# schematicEagle.net
KiCad netlist of a schematic drawn in EAGLE
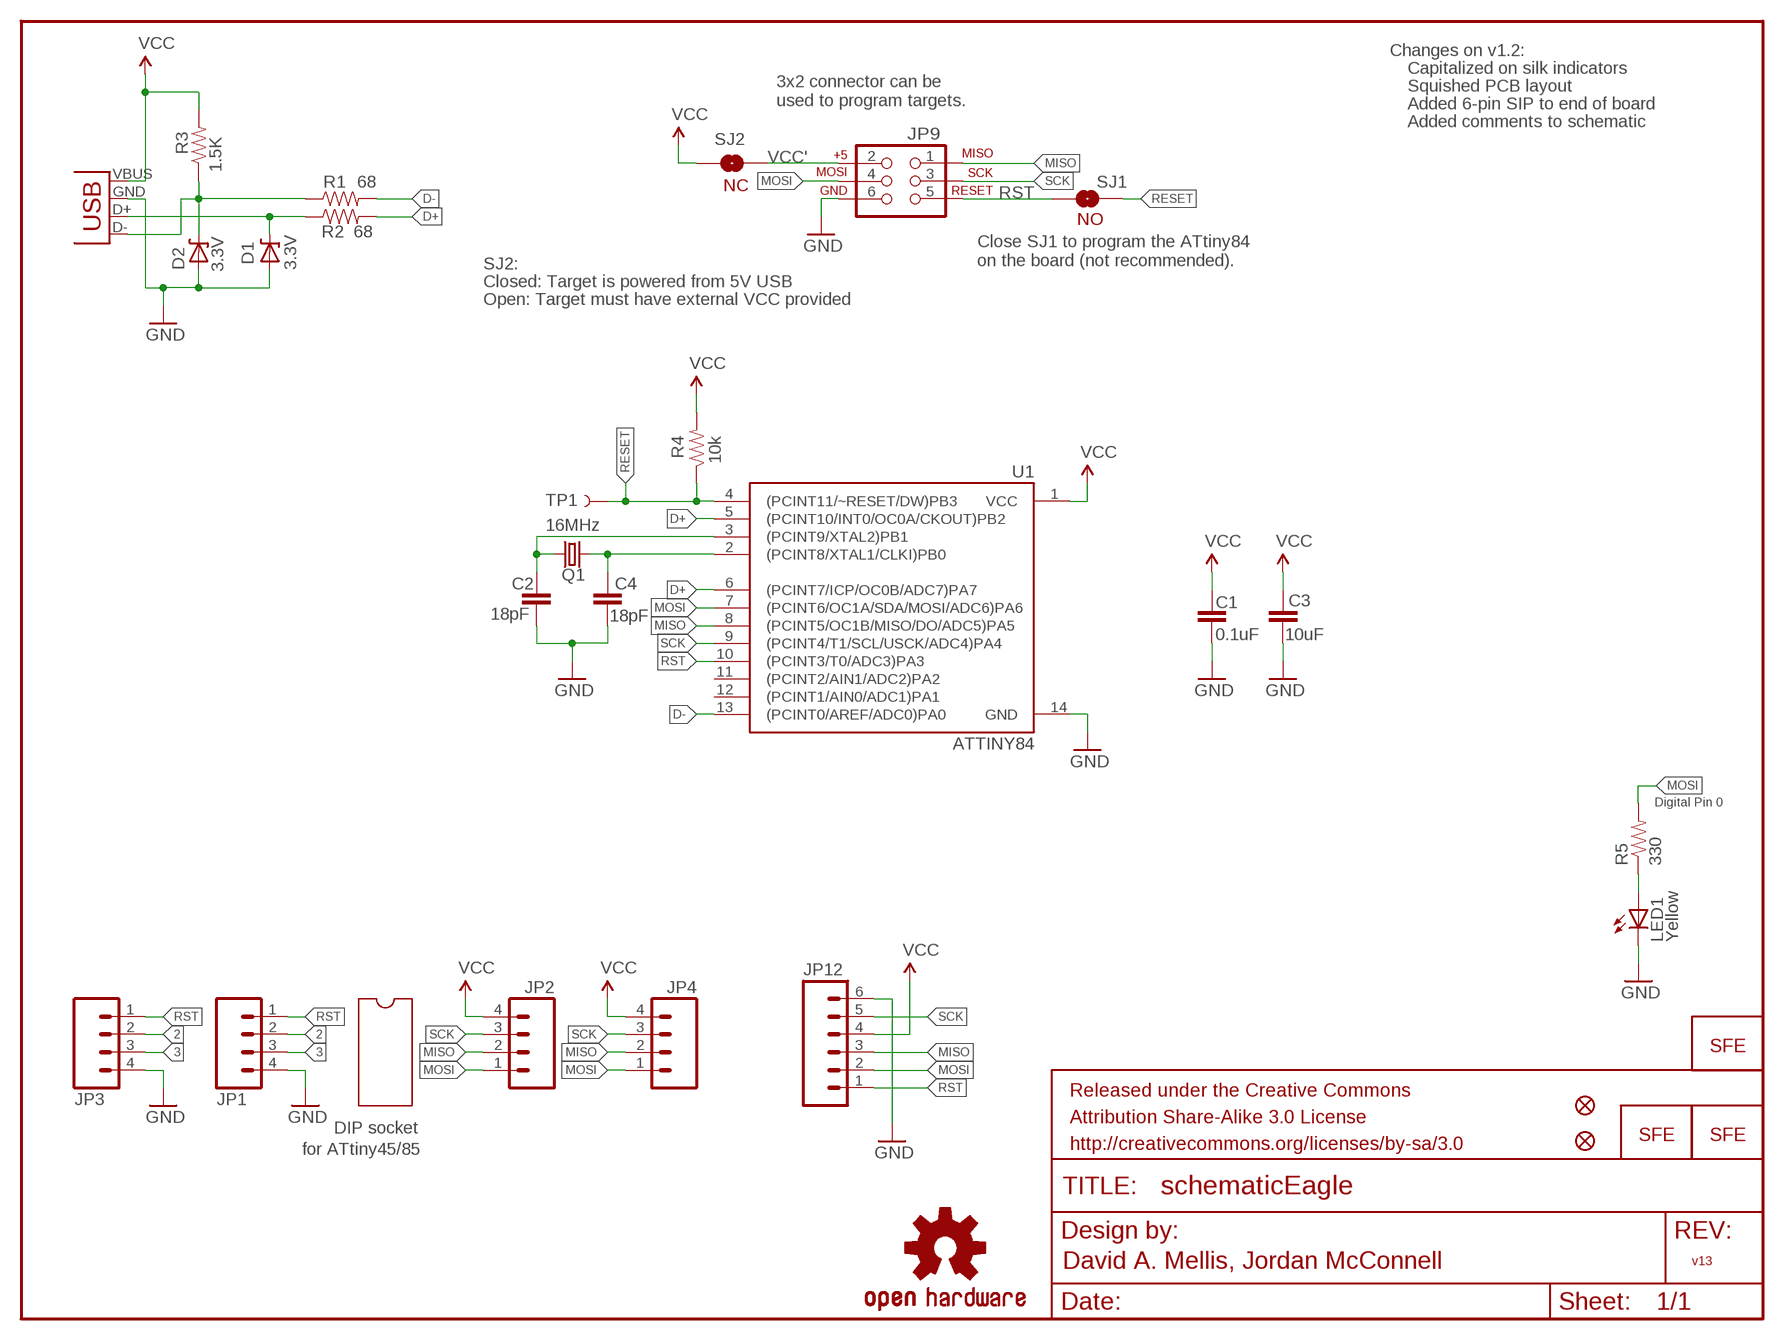
[diagram p0: schematic, sheet 1]

(export (version "E")
  (design (tool "Eeschema 10.0.6"))
  (components
    (comp (ref "C1")
      (value "0.1uF")
      (footprint "eagle-import:0402-CAP")
      (libsource (lib "eagle-import") (part "CAP0402-CAP"))
    )
    (comp (ref "C2")
      (value "18pF")
      (footprint "eagle-import:0402-CAP")
      (libsource (lib "eagle-import") (part "CAP0402-CAP"))
    )
    (comp (ref "C3")
      (value "10uF")
      (footprint "eagle-import:0402-CAP")
      (libsource (lib "eagle-import") (part "CAP0402-CAP"))
    )
    (comp (ref "C4")
      (value "18pF")
      (footprint "eagle-import:0402-CAP")
      (libsource (lib "eagle-import") (part "CAP0402-CAP"))
    )
    (comp (ref "D1")
      (value "3.3V")
      (footprint "eagle-import:SOD-323")
      (libsource (lib "eagle-import") (part "DIODE-ZENER-BZT52"))
    )
    (comp (ref "D2")
      (value "3.3V")
      (footprint "eagle-import:SOD-323")
      (libsource (lib "eagle-import") (part "DIODE-ZENER-BZT52"))
    )
    (comp (ref "FRAME1")
      (value "FRAME-LETTER")
      (footprint "eagle-import:CREATIVE_COMMONS")
      (libsource (lib "eagle-import") (part "FRAME-LETTER"))
    )
    (comp (ref "JP1")
      (value "M04PTH")
      (footprint "eagle-import:1X04")
      (libsource (lib "eagle-import") (part "M04PTH"))
    )
    (comp (ref "JP2")
      (value "M04PTH")
      (footprint "eagle-import:1X04")
      (libsource (lib "eagle-import") (part "M04PTH"))
    )
    (comp (ref "JP3")
      (value "M04SMD_STRAIGHT_COMBO")
      (footprint "eagle-import:1X04_SMD_STRAIGHT_COMBO")
      (libsource (lib "eagle-import") (part "M04SMD_STRAIGHT_COMBO"))
    )
    (comp (ref "JP4")
      (value "M04SMD_STRAIGHT_COMBO")
      (footprint "eagle-import:1X04_SMD_STRAIGHT_COMBO")
      (libsource (lib "eagle-import") (part "M04SMD_STRAIGHT_COMBO"))
    )
    (comp (ref "JP5")
      (value "LOGO-SFENW2")
      (footprint "eagle-import:SFE-NEW-WEB")
      (libsource (lib "eagle-import") (part "LOGO-SFENW2"))
    )
    (comp (ref "JP6")
      (value "LOGO-SFESK")
      (footprint "eagle-import:SFE-LOGO-FLAME")
      (libsource (lib "eagle-import") (part "LOGO-SFESK"))
    )
    (comp (ref "JP7")
      (value "FIDUCIALUFIDUCIAL")
      (footprint "eagle-import:MICRO-FIDUCIAL")
      (libsource (lib "eagle-import") (part "FIDUCIALUFIDUCIAL"))
    )
    (comp (ref "JP8")
      (value "FIDUCIALUFIDUCIAL")
      (footprint "eagle-import:MICRO-FIDUCIAL")
      (libsource (lib "eagle-import") (part "FIDUCIALUFIDUCIAL"))
    )
    (comp (ref "JP9")
      (value "AVR_SPI_PRG_6PTH")
      (footprint "eagle-import:2X3")
      (libsource (lib "eagle-import") (part "AVR_SPI_PRG_6PTH"))
    )
    (comp (ref "JP11")
      (value "LOGO-SFESK")
      (footprint "eagle-import:SFE-LOGO-FLAME")
      (libsource (lib "eagle-import") (part "LOGO-SFESK"))
    )
    (comp (ref "JP12")
      (value "M06SIP")
      (footprint "eagle-import:1X06")
      (libsource (lib "eagle-import") (part "M06SIP"))
    )
    (comp (ref "LED1")
      (value "Yellow")
      (footprint "eagle-import:LED-0603")
      (libsource (lib "eagle-import") (part "LED0603"))
    )
    (comp (ref "Q1")
      (value "16MHz")
      (footprint "eagle-import:CRYSTAL-SMD-5X3")
      (libsource (lib "eagle-import") (part "CRYSTAL5X3"))
    )
    (comp (ref "R1")
      (value "68")
      (footprint "eagle-import:0402-RES")
      (libsource (lib "eagle-import") (part "RESISTOR0402-RES"))
    )
    (comp (ref "R2")
      (value "68")
      (footprint "eagle-import:0402-RES")
      (libsource (lib "eagle-import") (part "RESISTOR0402-RES"))
    )
    (comp (ref "R3")
      (value "1.5K")
      (footprint "eagle-import:0402-RES")
      (libsource (lib "eagle-import") (part "RESISTOR0402-RES"))
    )
    (comp (ref "R4")
      (value "10k")
      (footprint "eagle-import:0402-RES")
      (libsource (lib "eagle-import") (part "RESISTOR0402-RES"))
    )
    (comp (ref "R5")
      (value "330")
      (footprint "eagle-import:0402-RES")
      (libsource (lib "eagle-import") (part "RESISTOR0402-RES"))
    )
    (comp (ref "SJ1")
      (value "SOLDERJUMPERNO")
      (footprint "eagle-import:SJ_2S-NO")
      (libsource (lib "eagle-import") (part "SOLDERJUMPERNO"))
    )
    (comp (ref "SJ2")
      (value "NC")
      (footprint "eagle-import:SJ_2S")
      (libsource (lib "eagle-import") (part "SOLDERJUMPERNC"))
    )
    (comp (ref "TP1")
      (value "TEST-POINT3")
      (footprint "eagle-import:PAD.03X.03")
      (libsource (lib "eagle-import") (part "TEST-POINT3"))
    )
    (comp (ref "U$1")
      (value "OSHW-LOGOS")
      (footprint "eagle-import:OSHW-LOGO-S")
      (libsource (lib "eagle-import") (part "OSHW-LOGOS"))
    )
    (comp (ref "U1")
      (value "ATTINY84")
      (footprint "eagle-import:SO14")
      (libsource (lib "eagle-import") (part "ATTINY84"))
    )
    (comp (ref "X1")
      (value "USB-A-H")
      (footprint "eagle-import:USB-A-H")
      (libsource (lib "eagle-import") (part "USB-A-H"))
    )
  )
  (nets
    (net (code "1") (name "/VCC'") (class "Default")
      (node (ref "JP9") (pin "2") (pinfunction "2_2") (pintype "passive"))
      (node (ref "SJ2") (pin "2") (pinfunction "2_2") (pintype "passive"))
    )
    (net (code "2") (name "2") (class "Default")
      (node (ref "JP1") (pin "2") (pinfunction "2_2") (pintype "passive"))
      (node (ref "JP3") (pin "2") (pinfunction "2_2") (pintype "passive"))
    )
    (net (code "3") (name "3") (class "Default")
      (node (ref "JP1") (pin "3") (pinfunction "3_3") (pintype "passive"))
      (node (ref "JP3") (pin "3") (pinfunction "3_3") (pintype "passive"))
    )
    (net (code "4") (name "D+") (class "Default")
      (node (ref "R2") (pin "2") (pinfunction "2_2") (pintype "passive"))
      (node (ref "U1") (pin "5") (pinfunction "(PCINT10/INT0/OC0A/CKOUT)PB2_5") (pintype "bidirectional"))
      (node (ref "U1") (pin "6") (pinfunction "(PCINT7/ICP/OC0B/ADC7)PA7_6") (pintype "bidirectional"))
    )
    (net (code "5") (name "D-") (class "Default")
      (node (ref "R1") (pin "2") (pinfunction "2_2") (pintype "passive"))
      (node (ref "U1") (pin "13") (pinfunction "(PCINT0/AREF/ADC0)PA0_13") (pintype "bidirectional"))
    )
    (net (code "6") (name "GND") (class "Default")
      (node (ref "C1") (pin "2") (pinfunction "2_2") (pintype "passive"))
      (node (ref "C2") (pin "2") (pinfunction "2_2") (pintype "passive"))
      (node (ref "C3") (pin "2") (pinfunction "2_2") (pintype "passive"))
      (node (ref "C4") (pin "2") (pinfunction "2_2") (pintype "passive"))
      (node (ref "D1") (pin "2") (pinfunction "A_2") (pintype "passive"))
      (node (ref "D2") (pin "2") (pinfunction "A_2") (pintype "passive"))
      (node (ref "JP1") (pin "4") (pinfunction "4_4") (pintype "passive"))
      (node (ref "JP12") (pin "6") (pinfunction "6_6") (pintype "passive"))
      (node (ref "JP3") (pin "4") (pinfunction "4_4") (pintype "passive"))
      (node (ref "JP9") (pin "6") (pinfunction "6_6") (pintype "passive"))
      (node (ref "LED1") (pin "C") (pinfunction "C_C") (pintype "passive"))
      (node (ref "U1") (pin "14") (pinfunction "GND_14") (pintype "bidirectional"))
      (node (ref "X1") (pin "GND") (pinfunction "VBUS_GND") (pintype "bidirectional"))
    )
    (net (code "7") (name "MISO") (class "Default")
      (node (ref "JP12") (pin "3") (pinfunction "3_3") (pintype "passive"))
      (node (ref "JP2") (pin "2") (pinfunction "2_2") (pintype "passive"))
      (node (ref "JP4") (pin "2") (pinfunction "2_2") (pintype "passive"))
      (node (ref "JP9") (pin "1") (pinfunction "1_1") (pintype "passive"))
      (node (ref "U1") (pin "8") (pinfunction "(PCINT5/OC1B/MISO/DO/ADC5)PA5_8") (pintype "bidirectional"))
    )
    (net (code "8") (name "MOSI") (class "Default")
      (node (ref "JP12") (pin "2") (pinfunction "2_2") (pintype "passive"))
      (node (ref "JP2") (pin "1") (pinfunction "1_1") (pintype "passive"))
      (node (ref "JP4") (pin "1") (pinfunction "1_1") (pintype "passive"))
      (node (ref "JP9") (pin "4") (pinfunction "4_4") (pintype "passive"))
      (node (ref "R5") (pin "2") (pinfunction "2_2") (pintype "passive"))
      (node (ref "U1") (pin "7") (pinfunction "(PCINT6/OC1A/SDA/MOSI/ADC6)PA6_7") (pintype "bidirectional"))
    )
    (net (code "9") (name "Net-(D1-C)") (class "Default")
      (node (ref "D1") (pin "1") (pinfunction "C_1") (pintype "passive"))
      (node (ref "R2") (pin "1") (pinfunction "1_1") (pintype "passive"))
      (node (ref "X1") (pin "D+") (pinfunction "D-_D+") (pintype "bidirectional"))
    )
    (net (code "10") (name "Net-(D2-C)") (class "Default")
      (node (ref "D2") (pin "1") (pinfunction "C_1") (pintype "passive"))
      (node (ref "R1") (pin "1") (pinfunction "1_1") (pintype "passive"))
      (node (ref "R3") (pin "1") (pinfunction "1_1") (pintype "passive"))
      (node (ref "X1") (pin "D-") (pinfunction "D+_D-") (pintype "bidirectional"))
    )
    (net (code "11") (name "Net-(LED1-PadA)") (class "Default")
      (node (ref "LED1") (pin "A") (pinfunction "A_A") (pintype "passive"))
      (node (ref "R5") (pin "1") (pinfunction "1_1") (pintype "passive"))
    )
    (net (code "12") (name "Net-(Q1-2)") (class "Default")
      (node (ref "C2") (pin "1") (pinfunction "1_1") (pintype "passive"))
      (node (ref "Q1") (pin "3") (pinfunction "2_3") (pintype "passive"))
      (node (ref "U1") (pin "3") (pinfunction "(PCINT9/XTAL2)PB1_3") (pintype "bidirectional"))
    )
    (net (code "13") (name "Net-(U1-(PCINT8{slash}XTAL1{slash}CLKI)PB0)") (class "Default")
      (node (ref "C4") (pin "1") (pinfunction "1_1") (pintype "passive"))
      (node (ref "Q1") (pin "1") (pinfunction "1_1") (pintype "passive"))
      (node (ref "U1") (pin "2") (pinfunction "(PCINT8/XTAL1/CLKI)PB0_2") (pintype "bidirectional"))
    )
    (net (code "14") (name "RESET") (class "Default")
      (node (ref "R4") (pin "1") (pinfunction "1_1") (pintype "passive"))
      (node (ref "SJ1") (pin "1") (pinfunction "1_1") (pintype "passive"))
      (node (ref "TP1") (pin "P$1") (pinfunction "1_P$1") (pintype "bidirectional"))
      (node (ref "U1") (pin "4") (pinfunction "(PCINT11/~{RESET/DW})PB3_4") (pintype "bidirectional"))
    )
    (net (code "15") (name "RST") (class "Default")
      (node (ref "JP1") (pin "1") (pinfunction "1_1") (pintype "passive"))
      (node (ref "JP12") (pin "1") (pinfunction "1_1") (pintype "passive"))
      (node (ref "JP3") (pin "1") (pinfunction "1_1") (pintype "passive"))
      (node (ref "JP9") (pin "5") (pinfunction "5_5") (pintype "passive"))
      (node (ref "SJ1") (pin "2") (pinfunction "2_2") (pintype "passive"))
      (node (ref "U1") (pin "10") (pinfunction "(PCINT3/T0/ADC3)PA3_10") (pintype "bidirectional"))
    )
    (net (code "16") (name "SCK") (class "Default")
      (node (ref "JP12") (pin "5") (pinfunction "5_5") (pintype "passive"))
      (node (ref "JP2") (pin "3") (pinfunction "3_3") (pintype "passive"))
      (node (ref "JP4") (pin "3") (pinfunction "3_3") (pintype "passive"))
      (node (ref "JP9") (pin "3") (pinfunction "3_3") (pintype "passive"))
      (node (ref "U1") (pin "9") (pinfunction "(PCINT4/T1/SCL/USCK/ADC4)PA4_9") (pintype "bidirectional"))
    )
    (net (code "17") (name "VCC") (class "Default")
      (node (ref "C1") (pin "1") (pinfunction "1_1") (pintype "passive"))
      (node (ref "C3") (pin "1") (pinfunction "1_1") (pintype "passive"))
      (node (ref "JP12") (pin "4") (pinfunction "4_4") (pintype "passive"))
      (node (ref "JP2") (pin "4") (pinfunction "4_4") (pintype "passive"))
      (node (ref "JP4") (pin "4") (pinfunction "4_4") (pintype "passive"))
      (node (ref "R3") (pin "2") (pinfunction "2_2") (pintype "passive"))
      (node (ref "R4") (pin "2") (pinfunction "2_2") (pintype "passive"))
      (node (ref "SJ2") (pin "1") (pinfunction "1_1") (pintype "passive"))
      (node (ref "U1") (pin "1") (pinfunction "VCC_1") (pintype "bidirectional"))
      (node (ref "X1") (pin "VBUS") (pinfunction "GND_VBUS") (pintype "bidirectional"))
    )
    (net (code "18") (name "unconnected-(U1-(PCINT1{slash}AIN0{slash}ADC1)PA1-Pad12)") (class "Default")
      (node (ref "U1") (pin "12") (pinfunction "(PCINT1/AIN0/ADC1)PA1_12") (pintype "bidirectional"))
    )
    (net (code "19") (name "unconnected-(U1-(PCINT2{slash}AIN1{slash}ADC2)PA2-Pad11)") (class "Default")
      (node (ref "U1") (pin "11") (pinfunction "(PCINT2/AIN1/ADC2)PA2_11") (pintype "bidirectional"))
    )
  )
)
